# TPS6209733_Buck_2A_3V3_FixedOutput.net
KiCad netlist of a schematic drawn in Altium Designer
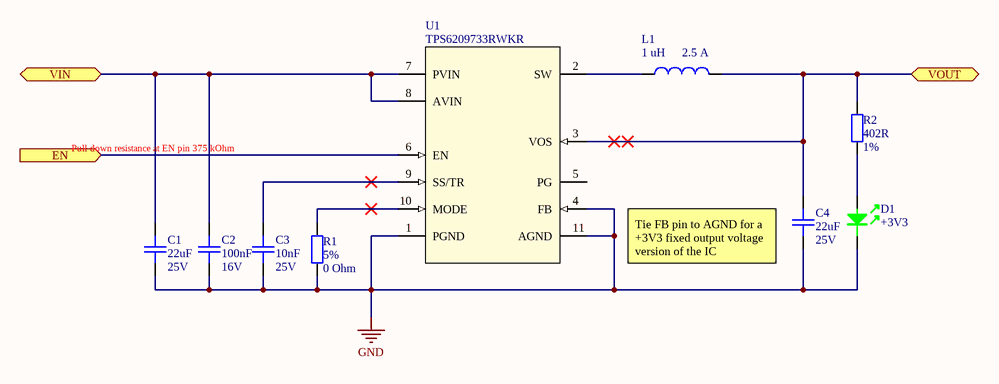
[diagram p0: TPS6209733_Buck_2A_3V3_FixedOutput.SchDoc]

(export (version "E")
  (design (tool "Eeschema 10.0.6"))
  (components
    (comp (ref "C1")
      (value "CAP CER 22UF 25V X5R 0805")
      (footprint "C0805")
      (description "22µF ±20% 25V Ceramic Capacitor X5R 0805 (2012 Metric)")
      (fields
        (field (name "MANUFACTURER") "Yageo")
        (field (name "MANUFACTURER PART NUMBER") "CC0805MKX5R8BB226")
        (field (name "CAPACITANCE") "22uF")
        (field (name "VOLTAGE RATING") "25V")
      )
      (libsource (lib "capacitors_smd") (part "CAP CER 22UF 25V X5R 0805"))
    )
    (comp (ref "C2")
      (value "CAP CER 0.1UF 16V X7R 0402")
      (footprint "C0402")
      (description "0.1µF ±10% 16V Ceramic Capacitor X7R 0402 (1005 Metric)")
      (fields
        (field (name "MANUFACTURER PART NUMBER") "CC0402KRX7R7BB104")
        (field (name "MANUFACTURER") "Yageo")
        (field (name "CAPACITANCE") "100nF")
        (field (name "VOLTAGE") "16V")
      )
      (libsource (lib "capacitors_smd") (part "CAP CER 0.1UF 16V X7R 0402"))
    )
    (comp (ref "C3")
      (value "CAP CER 10nF 25V X7R 10% 0402")
      (footprint "C0402")
      (description "Cap Cer 10nF 25V X7R 10% 0402")
      (fields
        (field (name "MANUFACTURER") "Kyocera AVX")
        (field (name "MANUFACTURER PART NUMBER") "04023C103KAT2A")
        (field (name "CAPACITANCE") "10nF")
        (field (name "VOLTAGE") "25V")
      )
      (libsource (lib "capacitors_smd") (part "CAP CER 10nF 25V X7R 10% 0402"))
    )
    (comp (ref "C4")
      (value "CAP CER 22UF 25V X5R 0805")
      (footprint "C0805")
      (description "22µF ±20% 25V Ceramic Capacitor X5R 0805 (2012 Metric)")
      (fields
        (field (name "MANUFACTURER") "Yageo")
        (field (name "MANUFACTURER PART NUMBER") "CC0805MKX5R8BB226")
        (field (name "CAPACITANCE") "22uF")
        (field (name "VOLTAGE RATING") "25V")
      )
      (libsource (lib "capacitors_smd") (part "CAP CER 22UF 25V X5R 0805"))
    )
    (comp (ref "D1")
      (value "+3V3")
      (footprint "LED_0603")
      (description "Green 571nm LED Indication - Discrete 2V 0603 (1608 Metric)")
      (fields
        (field (name "MANUFACTURER") "Vishay Lite-On")
        (field (name "MANUFACTURER PART NUMBER") "LTST-C191KGKT")
      )
      (libsource (lib "diodes_led") (part "LED GREEN CLEAR 0603 SMD"))
    )
    (comp (ref "L1")
      (value "FIXED IND 1UH 2.5A 75 MOHM SMD")
      (footprint "74438323010")
      (description "1µH Shielded Molded Inductor 2.5A 75mOhm Max 1008 (2520 Metric)")
      (fields
        (field (name "MANUFACTURER") "Wurth Elektronik")
        (field (name "MANUFACTURER PART NUMBER") "74438323010")
        (field (name "INDUCTANCE") "1 uH")
        (field (name "MAXIMUM DC CURRENT") "2.5 A")
      )
      (libsource (lib "inductors_smd") (part "FIXED IND 1UH 2.5A 75 MOHM SMD"))
    )
    (comp (ref "R1")
      (value "RES SMD 0 OHM JUMPER 1/16W 0402")
      (footprint "R0402")
      (description "0 Ohms Jumper 0.063W, 1/16W Chip Resistor 0402 (1005 Metric) Moisture Resistant Thick Film")
      (fields
        (field (name "TOLERANCE") "5%")
        (field (name "RESISTANCE") "0 Ohm")
        (field (name "MANUFACTURER") "Yageo")
        (field (name "MANUFACTURER PART NUMBER") "RC0402JR-070RL")
      )
      (libsource (lib "resistors_smd") (part "RES SMD 0 OHM JUMPER 1/16W 0402"))
    )
    (comp (ref "R2")
      (value "RES SMD 402 OHM 1% 1/16W 0402")
      (footprint "R0402")
      (description "402 Ohms ±1% 0.063W, 1/16W Chip Resistor 0402 (1005 Metric) Moisture Resistant Thick Film")
      (fields
        (field (name "MANUFACTURER") "Yageo")
        (field (name "MANUFACTURER PART NUMBER") "RC0402FR-07402RL")
        (field (name "RESISTANCE") "402R")
        (field (name "TOLERANCE") "1%")
      )
      (libsource (lib "resistors_smd") (part "RES SMD 402 OHM 1% 1/16W 0402"))
    )
    (comp (ref "U1")
      (value "TPS6209733RWKR")
      (footprint "RWK11")
      (description "Buck Switching Regulator IC Positive Fixed 3.3V 1 Output 2A 11-VFQFN")
      (fields (field (name "MANUFACTURER") "Texas Instruments"))
      (libsource (lib "dcdc_converters") (part "IC TPS6209733 REG BUCK FIXED 3.3V 2A 11VQFN"))
    )
  )
  (nets
    (net (code "1") (name "/EN") (class "Default")
      (node (ref "U1") (pin "6") (pinfunction "EN_6") (pintype "input"))
    )
    (net (code "2") (name "/VIN") (class "Default")
      (node (ref "C1") (pin "1") (pinfunction "1_1") (pintype "passive"))
      (node (ref "C2") (pin "2") (pinfunction "2_2") (pintype "passive"))
      (node (ref "U1") (pin "7") (pinfunction "PVIN_7") (pintype "power_in"))
      (node (ref "U1") (pin "8") (pinfunction "AVIN_8") (pintype "power_in"))
    )
    (net (code "3") (name "/VOUT") (class "Default")
      (node (ref "C4") (pin "1") (pinfunction "1_1") (pintype "passive"))
      (node (ref "L1") (pin "2") (pinfunction "2_2") (pintype "passive"))
      (node (ref "R2") (pin "2") (pinfunction "2_2") (pintype "passive"))
      (node (ref "U1") (pin "3") (pinfunction "VOS_3") (pintype "input"))
    )
    (net (code "4") (name "GND") (class "Default")
      (node (ref "C1") (pin "2") (pinfunction "2_2") (pintype "passive"))
      (node (ref "C2") (pin "1") (pinfunction "1_1") (pintype "passive"))
      (node (ref "C3") (pin "1") (pinfunction "1_1") (pintype "passive"))
      (node (ref "C4") (pin "2") (pinfunction "2_2") (pintype "passive"))
      (node (ref "D1") (pin "1") (pinfunction "K_1") (pintype "passive"))
      (node (ref "R1") (pin "1") (pinfunction "1_1") (pintype "passive"))
      (node (ref "U1") (pin "1") (pinfunction "PGND_1") (pintype "power_in"))
      (node (ref "U1") (pin "11") (pinfunction "AGND_11") (pintype "power_in"))
      (node (ref "U1") (pin "4") (pinfunction "FB_4") (pintype "input"))
    )
    (net (code "5") (name "Net-(D1-A)") (class "Default")
      (node (ref "D1") (pin "2") (pinfunction "A_2") (pintype "passive"))
      (node (ref "R2") (pin "1") (pinfunction "1_1") (pintype "passive"))
    )
    (net (code "6") (name "Net-(U1-MODE)") (class "Default")
      (node (ref "R1") (pin "2") (pinfunction "2_2") (pintype "passive"))
      (node (ref "U1") (pin "10") (pinfunction "MODE_10") (pintype "input"))
    )
    (net (code "7") (name "Net-(U1-SS{slash}TR)") (class "Default")
      (node (ref "C3") (pin "2") (pinfunction "2_2") (pintype "passive"))
      (node (ref "U1") (pin "9") (pinfunction "SS/TR_9") (pintype "input"))
    )
    (net (code "8") (name "Net-(U1-SW)") (class "Default")
      (node (ref "L1") (pin "1") (pinfunction "1_1") (pintype "passive"))
      (node (ref "U1") (pin "2") (pinfunction "SW_2") (pintype "power_in"))
    )
    (net (code "9") (name "unconnected-(U1-PG-Pad5)") (class "Default")
      (node (ref "U1") (pin "5") (pinfunction "PG_5") (pintype "open_collector"))
    )
  )
)
